# AVR.net
KiCad netlist of a schematic drawn in EAGLE
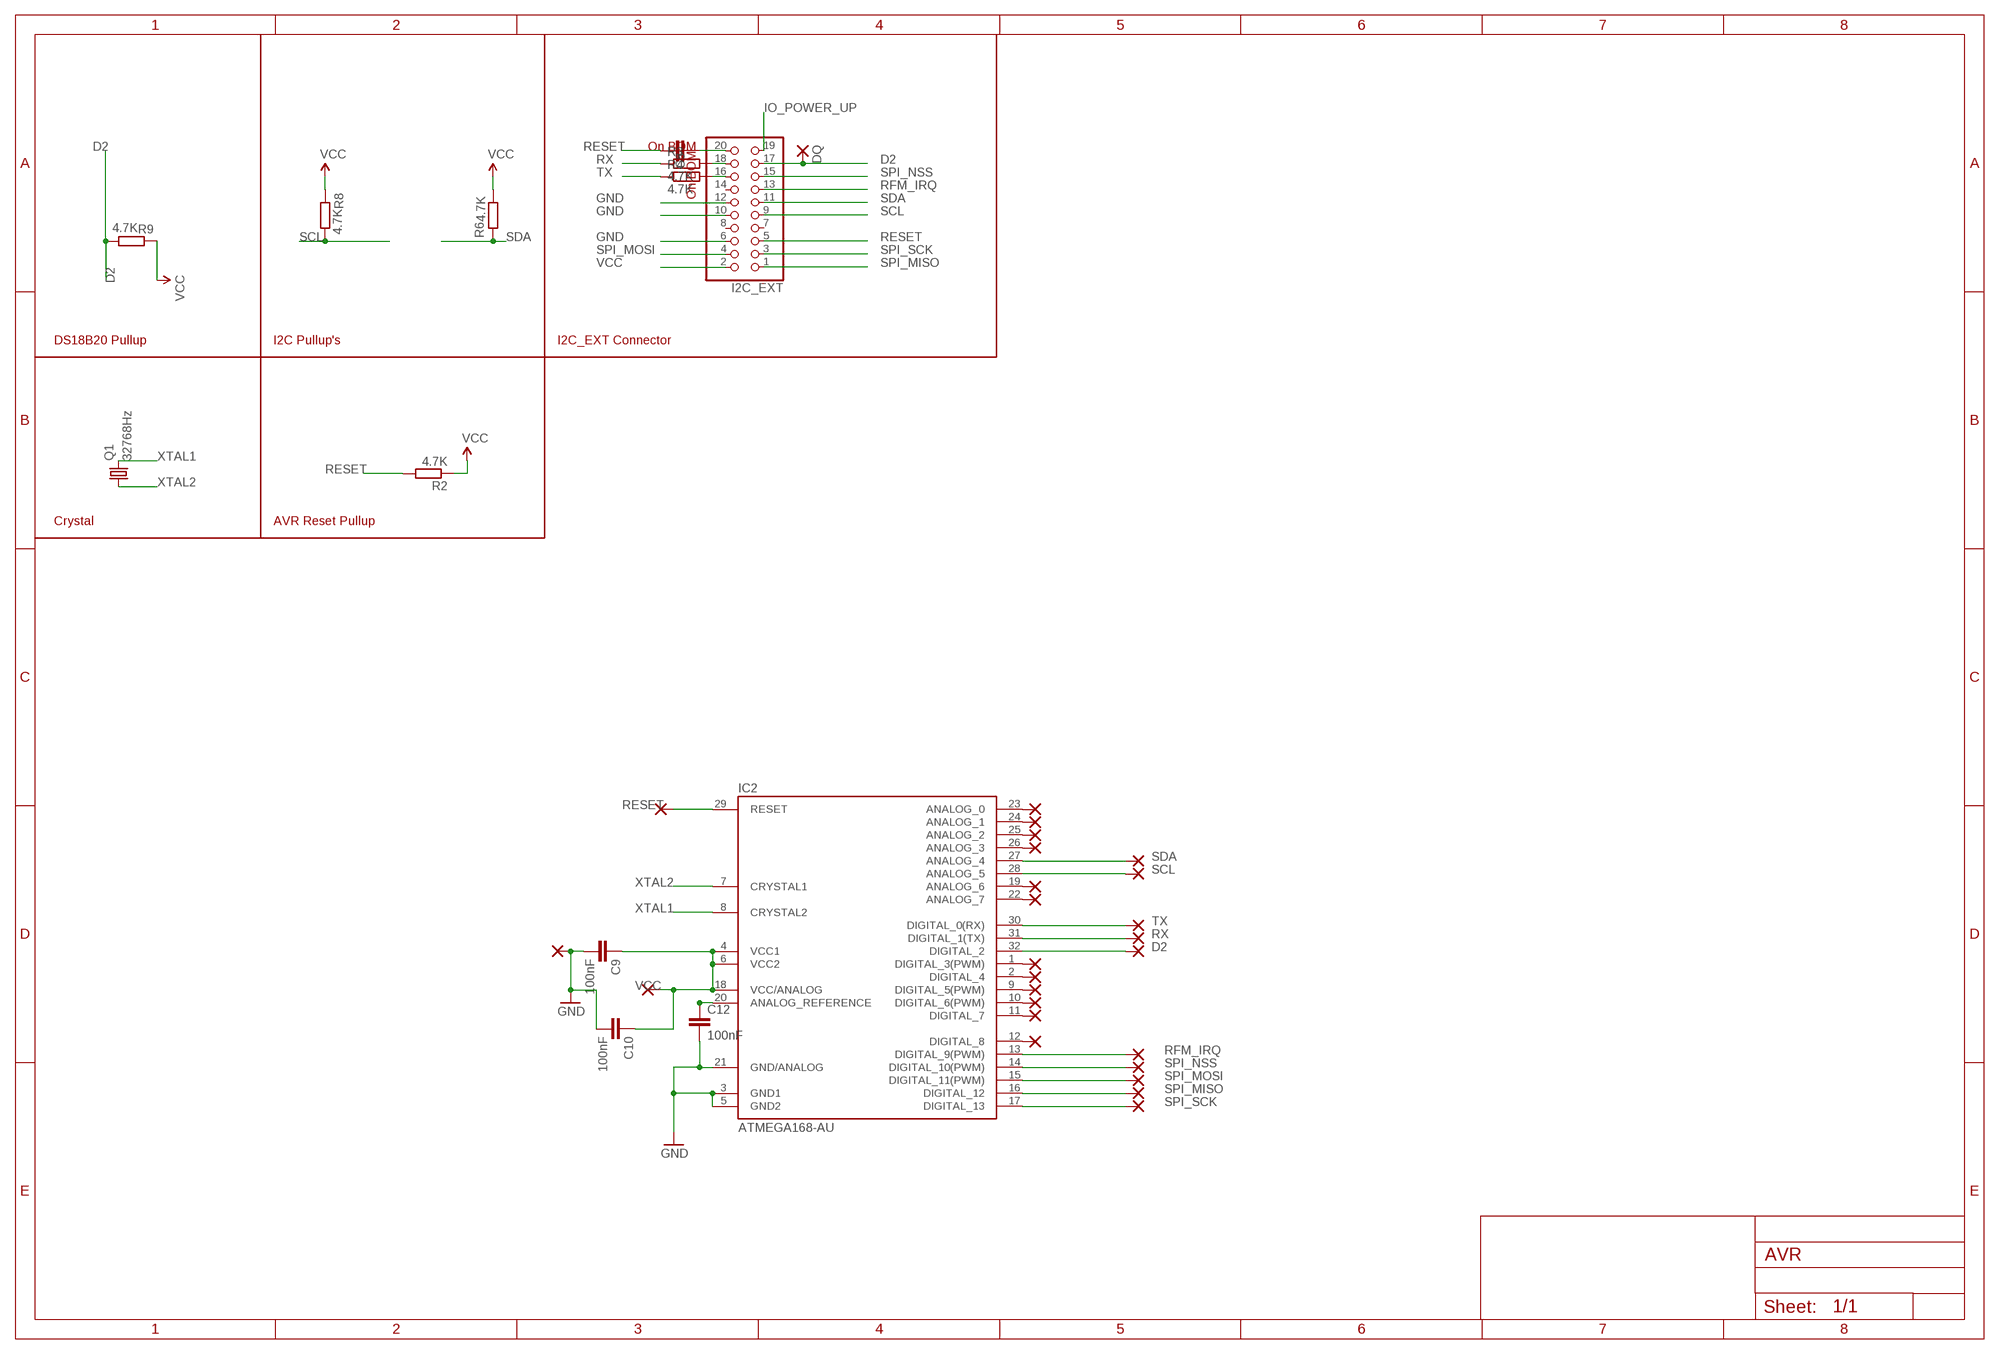
[diagram p0: schematic, sheet 1]

(export (version "E")
  (design (tool "Eeschema 10.0.6"))
  (components
    (comp (ref "C5")
      (value "100nF")
      (footprint "eagle-import:C0603")
      (libsource (lib "eagle-import") (part "C-EUC0603"))
    )
    (comp (ref "C9")
      (value "100nF")
      (footprint "eagle-import:C0603")
      (libsource (lib "eagle-import") (part "C-EUC0603"))
    )
    (comp (ref "C10")
      (value "100nF")
      (footprint "eagle-import:C0603")
      (libsource (lib "eagle-import") (part "C-EUC0603"))
    )
    (comp (ref "C12")
      (value "100nF")
      (footprint "eagle-import:C0603")
      (libsource (lib "eagle-import") (part "C-EUC0603"))
    )
    (comp (ref "DQ")
      (value "2,15/1,0")
      (footprint "eagle-import:2,15_1,0")
      (libsource (lib "eagle-import") (part "2,15/1,0"))
    )
    (comp (ref "I2C_EXT")
      (value "PINHD-2X10")
      (footprint "eagle-import:2X10")
      (libsource (lib "eagle-import") (part "PINHD-2X10"))
    )
    (comp (ref "IC2")
      (value "ATMEGA168-AU")
      (footprint "eagle-import:TQFP32-08")
      (libsource (lib "eagle-import") (part "ATMEGA168-AU"))
    )
    (comp (ref "PAD1")
      (value "1,6/0,8")
      (footprint "eagle-import:1,6_0,8")
      (libsource (lib "eagle-import") (part "1,6/0,8"))
    )
    (comp (ref "PAD2")
      (value "1,6/0,8")
      (footprint "eagle-import:1,6_0,8")
      (libsource (lib "eagle-import") (part "1,6/0,8"))
    )
    (comp (ref "PAD3")
      (value "1,6/0,8")
      (footprint "eagle-import:1,6_0,8")
      (libsource (lib "eagle-import") (part "1,6/0,8"))
    )
    (comp (ref "PAD4")
      (value "1,6/0,8")
      (footprint "eagle-import:1,6_0,8")
      (libsource (lib "eagle-import") (part "1,6/0,8"))
    )
    (comp (ref "PAD5")
      (value "1,6/0,8")
      (footprint "eagle-import:1,6_0,8")
      (libsource (lib "eagle-import") (part "1,6/0,8"))
    )
    (comp (ref "PAD6")
      (value "1,6/0,8")
      (footprint "eagle-import:1,6_0,8")
      (libsource (lib "eagle-import") (part "1,6/0,8"))
    )
    (comp (ref "PAD7")
      (value "1,6/0,8")
      (footprint "eagle-import:1,6_0,8")
      (libsource (lib "eagle-import") (part "1,6/0,8"))
    )
    (comp (ref "PAD8")
      (value "1,6/0,8")
      (footprint "eagle-import:1,6_0,8")
      (libsource (lib "eagle-import") (part "1,6/0,8"))
    )
    (comp (ref "PAD9")
      (value "1,6/0,8")
      (footprint "eagle-import:1,6_0,8")
      (libsource (lib "eagle-import") (part "1,6/0,8"))
    )
    (comp (ref "PAD10")
      (value "1,6/0,8")
      (footprint "eagle-import:1,6_0,8")
      (libsource (lib "eagle-import") (part "1,6/0,8"))
    )
    (comp (ref "PAD11")
      (value "1,6/0,8")
      (footprint "eagle-import:1,6_0,8")
      (libsource (lib "eagle-import") (part "1,6/0,8"))
    )
    (comp (ref "PAD12")
      (value "1,6/0,8")
      (footprint "eagle-import:1,6_0,8")
      (libsource (lib "eagle-import") (part "1,6/0,8"))
    )
    (comp (ref "PAD13")
      (value "1,6/0,8")
      (footprint "eagle-import:1,6_0,8")
      (libsource (lib "eagle-import") (part "1,6/0,8"))
    )
    (comp (ref "PAD14")
      (value "1,6/0,8")
      (footprint "eagle-import:1,6_0,8")
      (libsource (lib "eagle-import") (part "1,6/0,8"))
    )
    (comp (ref "PAD15")
      (value "1,6/0,8")
      (footprint "eagle-import:1,6_0,8")
      (libsource (lib "eagle-import") (part "1,6/0,8"))
    )
    (comp (ref "PAD16")
      (value "1,6/0,8")
      (footprint "eagle-import:1,6_0,8")
      (libsource (lib "eagle-import") (part "1,6/0,8"))
    )
    (comp (ref "PAD17")
      (value "1,6/0,8")
      (footprint "eagle-import:1,6_0,8")
      (libsource (lib "eagle-import") (part "1,6/0,8"))
    )
    (comp (ref "PAD18")
      (value "1,6/0,8")
      (footprint "eagle-import:1,6_0,8")
      (libsource (lib "eagle-import") (part "1,6/0,8"))
    )
    (comp (ref "PAD19")
      (value "1,6/0,8")
      (footprint "eagle-import:1,6_0,8")
      (libsource (lib "eagle-import") (part "1,6/0,8"))
    )
    (comp (ref "PAD20")
      (value "1,6/0,8")
      (footprint "eagle-import:1,6_0,8")
      (libsource (lib "eagle-import") (part "1,6/0,8"))
    )
    (comp (ref "PAD21")
      (value "1,6/0,8")
      (footprint "eagle-import:1,6_0,8")
      (libsource (lib "eagle-import") (part "1,6/0,8"))
    )
    (comp (ref "PAD22")
      (value "1,6/0,8")
      (footprint "eagle-import:1,6_0,8")
      (libsource (lib "eagle-import") (part "1,6/0,8"))
    )
    (comp (ref "PAD23")
      (value "1,6/0,8")
      (footprint "eagle-import:1,6_0,8")
      (libsource (lib "eagle-import") (part "1,6/0,8"))
    )
    (comp (ref "PAD24")
      (value "1,6/0,8")
      (footprint "eagle-import:1,6_0,8")
      (libsource (lib "eagle-import") (part "1,6/0,8"))
    )
    (comp (ref "PAD25")
      (value "1,6/0,8")
      (footprint "eagle-import:1,6_0,8")
      (libsource (lib "eagle-import") (part "1,6/0,8"))
    )
    (comp (ref "Q1")
      (value "32768Hz")
      (footprint "eagle-import:MC-306")
      (fields (field (name "MPN") "MC-306 60.0KHZ  100PPM ,12.5PF"))
      (libsource (lib "eagle-import") (part "MC-306"))
    )
    (comp (ref "R2")
      (value "4.7K")
      (footprint "eagle-import:R0603")
      (libsource (lib "eagle-import") (part "R-EU_R0603"))
    )
    (comp (ref "R3")
      (value "4.7K")
      (footprint "eagle-import:R0603")
      (libsource (lib "eagle-import") (part "R-EU_R0603"))
    )
    (comp (ref "R4")
      (value "4.7K")
      (footprint "eagle-import:R0603")
      (libsource (lib "eagle-import") (part "R-EU_R0603"))
    )
    (comp (ref "R6")
      (value "4.7K")
      (footprint "eagle-import:R0603")
      (libsource (lib "eagle-import") (part "R-EU_R0603"))
    )
    (comp (ref "R8")
      (value "4.7K")
      (footprint "eagle-import:R0603")
      (libsource (lib "eagle-import") (part "R-EU_R0603"))
    )
    (comp (ref "R9")
      (value "4.7K")
      (footprint "eagle-import:R0603")
      (libsource (lib "eagle-import") (part "R-EU_R0603"))
    )
  )
  (nets
    (net (code "1") (name "/D2") (class "Default")
      (node (ref "DQ") (pin "1") (pinfunction "P_1") (pintype "passive"))
      (node (ref "I2C_EXT") (pin "17") (pinfunction "17_17") (pintype "passive"))
      (node (ref "IC2") (pin "32") (pinfunction "DIGITAL_2_32") (pintype "bidirectional"))
      (node (ref "PAD14") (pin "1") (pinfunction "P_1") (pintype "passive"))
      (node (ref "R9") (pin "1") (pinfunction "1_1") (pintype "passive"))
    )
    (net (code "2") (name "/IO_POWER_UP") (class "Default")
      (node (ref "I2C_EXT") (pin "19") (pinfunction "19_19") (pintype "passive"))
    )
    (net (code "3") (name "/RESET") (class "Default")
      (node (ref "C5") (pin "1") (pinfunction "1_1") (pintype "passive"))
      (node (ref "I2C_EXT") (pin "5") (pinfunction "5_5") (pintype "passive"))
      (node (ref "IC2") (pin "29") (pinfunction "RESET_29") (pintype "bidirectional"))
      (node (ref "PAD1") (pin "1") (pinfunction "P_1") (pintype "passive"))
      (node (ref "R2") (pin "2") (pinfunction "2_2") (pintype "passive"))
    )
    (net (code "4") (name "/RFM_IRQ") (class "Default")
      (node (ref "I2C_EXT") (pin "13") (pinfunction "13_13") (pintype "passive"))
      (node (ref "IC2") (pin "13") (pinfunction "DIGITAL_9(PWM)_13") (pintype "bidirectional"))
      (node (ref "PAD21") (pin "1") (pinfunction "P_1") (pintype "passive"))
    )
    (net (code "5") (name "/RX") (class "Default")
      (node (ref "IC2") (pin "31") (pinfunction "DIGITAL_1(TX)_31") (pintype "bidirectional"))
      (node (ref "PAD13") (pin "1") (pinfunction "P_1") (pintype "passive"))
      (node (ref "R3") (pin "1") (pinfunction "1_1") (pintype "passive"))
    )
    (net (code "6") (name "/SCL") (class "Default")
      (node (ref "I2C_EXT") (pin "9") (pinfunction "9_9") (pintype "passive"))
      (node (ref "IC2") (pin "28") (pinfunction "ANALOG_5_28") (pintype "bidirectional"))
      (node (ref "PAD9") (pin "1") (pinfunction "P_1") (pintype "passive"))
      (node (ref "R8") (pin "1") (pinfunction "1_1") (pintype "passive"))
    )
    (net (code "7") (name "/SDA") (class "Default")
      (node (ref "I2C_EXT") (pin "11") (pinfunction "11_11") (pintype "passive"))
      (node (ref "IC2") (pin "27") (pinfunction "ANALOG_4_27") (pintype "bidirectional"))
      (node (ref "PAD8") (pin "1") (pinfunction "P_1") (pintype "passive"))
      (node (ref "R6") (pin "2") (pinfunction "2_2") (pintype "passive"))
    )
    (net (code "8") (name "/SPI_MISO") (class "Default")
      (node (ref "I2C_EXT") (pin "1") (pinfunction "1_1") (pintype "passive"))
      (node (ref "IC2") (pin "16") (pinfunction "DIGITAL_12_16") (pintype "bidirectional"))
      (node (ref "PAD24") (pin "1") (pinfunction "P_1") (pintype "passive"))
    )
    (net (code "9") (name "/SPI_MOSI") (class "Default")
      (node (ref "I2C_EXT") (pin "4") (pinfunction "4_4") (pintype "passive"))
      (node (ref "IC2") (pin "15") (pinfunction "DIGITAL_11(PWM)_15") (pintype "bidirectional"))
      (node (ref "PAD23") (pin "1") (pinfunction "P_1") (pintype "passive"))
    )
    (net (code "10") (name "/SPI_NSS") (class "Default")
      (node (ref "I2C_EXT") (pin "15") (pinfunction "15_15") (pintype "passive"))
      (node (ref "IC2") (pin "14") (pinfunction "DIGITAL_10(PWM)_14") (pintype "bidirectional"))
      (node (ref "PAD22") (pin "1") (pinfunction "P_1") (pintype "passive"))
    )
    (net (code "11") (name "/SPI_SCK") (class "Default")
      (node (ref "I2C_EXT") (pin "3") (pinfunction "3_3") (pintype "passive"))
      (node (ref "IC2") (pin "17") (pinfunction "DIGITAL_13_17") (pintype "bidirectional"))
      (node (ref "PAD25") (pin "1") (pinfunction "P_1") (pintype "passive"))
    )
    (net (code "12") (name "/TX") (class "Default")
      (node (ref "IC2") (pin "30") (pinfunction "DIGITAL_0(RX)_30") (pintype "bidirectional"))
      (node (ref "PAD12") (pin "1") (pinfunction "P_1") (pintype "passive"))
      (node (ref "R4") (pin "1") (pinfunction "1_1") (pintype "passive"))
    )
    (net (code "13") (name "/XTAL1") (class "Default")
      (node (ref "IC2") (pin "8") (pinfunction "CRYSTAL2_8") (pintype "bidirectional"))
      (node (ref "Q1") (pin "4") (pinfunction "2_4") (pintype "passive"))
    )
    (net (code "14") (name "/XTAL2") (class "Default")
      (node (ref "IC2") (pin "7") (pinfunction "CRYSTAL1_7") (pintype "bidirectional"))
      (node (ref "Q1") (pin "1") (pinfunction "1_1") (pintype "passive"))
    )
    (net (code "15") (name "GND") (class "Default")
      (node (ref "C10") (pin "2") (pinfunction "2_2") (pintype "passive"))
      (node (ref "C12") (pin "2") (pinfunction "2_2") (pintype "passive"))
      (node (ref "C9") (pin "2") (pinfunction "2_2") (pintype "passive"))
      (node (ref "I2C_EXT") (pin "10") (pinfunction "10_10") (pintype "passive"))
      (node (ref "I2C_EXT") (pin "12") (pinfunction "12_12") (pintype "passive"))
      (node (ref "I2C_EXT") (pin "6") (pinfunction "6_6") (pintype "passive"))
      (node (ref "IC2") (pin "21") (pinfunction "GND/ANALOG_21") (pintype "power_in"))
      (node (ref "IC2") (pin "3") (pinfunction "GND1_3") (pintype "power_in"))
      (node (ref "IC2") (pin "5") (pinfunction "GND2_5") (pintype "power_in"))
      (node (ref "PAD2") (pin "1") (pinfunction "P_1") (pintype "passive"))
    )
    (net (code "16") (name "Net-(C5-Pad2)") (class "Default")
      (node (ref "C5") (pin "2") (pinfunction "2_2") (pintype "passive"))
      (node (ref "I2C_EXT") (pin "20") (pinfunction "20_20") (pintype "passive"))
    )
    (net (code "17") (name "Net-(I2C_EXT-Pad16)") (class "Default")
      (node (ref "I2C_EXT") (pin "16") (pinfunction "16_16") (pintype "passive"))
      (node (ref "R4") (pin "2") (pinfunction "2_2") (pintype "passive"))
    )
    (net (code "18") (name "Net-(I2C_EXT-Pad18)") (class "Default")
      (node (ref "I2C_EXT") (pin "18") (pinfunction "18_18") (pintype "passive"))
      (node (ref "R3") (pin "2") (pinfunction "2_2") (pintype "passive"))
    )
    (net (code "19") (name "Net-(IC2-ANALOG_0)") (class "Default")
      (node (ref "IC2") (pin "23") (pinfunction "ANALOG_0_23") (pintype "bidirectional"))
      (node (ref "PAD4") (pin "1") (pinfunction "P_1") (pintype "passive"))
    )
    (net (code "20") (name "Net-(IC2-ANALOG_1)") (class "Default")
      (node (ref "IC2") (pin "24") (pinfunction "ANALOG_1_24") (pintype "bidirectional"))
      (node (ref "PAD5") (pin "1") (pinfunction "P_1") (pintype "passive"))
    )
    (net (code "21") (name "Net-(IC2-ANALOG_2)") (class "Default")
      (node (ref "IC2") (pin "25") (pinfunction "ANALOG_2_25") (pintype "bidirectional"))
      (node (ref "PAD6") (pin "1") (pinfunction "P_1") (pintype "passive"))
    )
    (net (code "22") (name "Net-(IC2-ANALOG_3)") (class "Default")
      (node (ref "IC2") (pin "26") (pinfunction "ANALOG_3_26") (pintype "bidirectional"))
      (node (ref "PAD7") (pin "1") (pinfunction "P_1") (pintype "passive"))
    )
    (net (code "23") (name "Net-(IC2-ANALOG_6)") (class "Default")
      (node (ref "IC2") (pin "19") (pinfunction "ANALOG_6_19") (pintype "passive"))
      (node (ref "PAD10") (pin "1") (pinfunction "P_1") (pintype "passive"))
    )
    (net (code "24") (name "Net-(IC2-ANALOG_7)") (class "Default")
      (node (ref "IC2") (pin "22") (pinfunction "ANALOG_7_22") (pintype "passive"))
      (node (ref "PAD11") (pin "1") (pinfunction "P_1") (pintype "passive"))
    )
    (net (code "25") (name "Net-(IC2-ANALOG_REFERENCE)") (class "Default")
      (node (ref "C12") (pin "1") (pinfunction "1_1") (pintype "passive"))
      (node (ref "IC2") (pin "20") (pinfunction "ANALOG_REFERENCE_20") (pintype "passive"))
    )
    (net (code "26") (name "Net-(IC2-DIGITAL_3(PWM))") (class "Default")
      (node (ref "IC2") (pin "1") (pinfunction "DIGITAL_3(PWM)_1") (pintype "bidirectional"))
      (node (ref "PAD15") (pin "1") (pinfunction "P_1") (pintype "passive"))
    )
    (net (code "27") (name "Net-(IC2-DIGITAL_4)") (class "Default")
      (node (ref "IC2") (pin "2") (pinfunction "DIGITAL_4_2") (pintype "bidirectional"))
      (node (ref "PAD16") (pin "1") (pinfunction "P_1") (pintype "passive"))
    )
    (net (code "28") (name "Net-(IC2-DIGITAL_5(PWM))") (class "Default")
      (node (ref "IC2") (pin "9") (pinfunction "DIGITAL_5(PWM)_9") (pintype "bidirectional"))
      (node (ref "PAD17") (pin "1") (pinfunction "P_1") (pintype "passive"))
    )
    (net (code "29") (name "Net-(IC2-DIGITAL_6(PWM))") (class "Default")
      (node (ref "IC2") (pin "10") (pinfunction "DIGITAL_6(PWM)_10") (pintype "bidirectional"))
      (node (ref "PAD18") (pin "1") (pinfunction "P_1") (pintype "passive"))
    )
    (net (code "30") (name "Net-(IC2-DIGITAL_7)") (class "Default")
      (node (ref "IC2") (pin "11") (pinfunction "DIGITAL_7_11") (pintype "bidirectional"))
      (node (ref "PAD19") (pin "1") (pinfunction "P_1") (pintype "passive"))
    )
    (net (code "31") (name "Net-(IC2-DIGITAL_8)") (class "Default")
      (node (ref "IC2") (pin "12") (pinfunction "DIGITAL_8_12") (pintype "bidirectional"))
      (node (ref "PAD20") (pin "1") (pinfunction "P_1") (pintype "passive"))
    )
    (net (code "32") (name "VCC") (class "Default")
      (node (ref "C10") (pin "1") (pinfunction "1_1") (pintype "passive"))
      (node (ref "C9") (pin "1") (pinfunction "1_1") (pintype "passive"))
      (node (ref "I2C_EXT") (pin "2") (pinfunction "2_2") (pintype "passive"))
      (node (ref "IC2") (pin "18") (pinfunction "VCC/ANALOG_18") (pintype "passive"))
      (node (ref "IC2") (pin "4") (pinfunction "VCC1_4") (pintype "power_in"))
      (node (ref "IC2") (pin "6") (pinfunction "VCC2_6") (pintype "power_in"))
      (node (ref "PAD3") (pin "1") (pinfunction "P_1") (pintype "passive"))
      (node (ref "R2") (pin "1") (pinfunction "1_1") (pintype "passive"))
      (node (ref "R6") (pin "1") (pinfunction "1_1") (pintype "passive"))
      (node (ref "R8") (pin "2") (pinfunction "2_2") (pintype "passive"))
      (node (ref "R9") (pin "2") (pinfunction "2_2") (pintype "passive"))
    )
    (net (code "33") (name "unconnected-(I2C_EXT-Pad7)") (class "Default")
      (node (ref "I2C_EXT") (pin "7") (pinfunction "7_7") (pintype "passive"))
    )
    (net (code "34") (name "unconnected-(I2C_EXT-Pad8)") (class "Default")
      (node (ref "I2C_EXT") (pin "8") (pinfunction "8_8") (pintype "passive"))
    )
    (net (code "35") (name "unconnected-(I2C_EXT-Pad14)") (class "Default")
      (node (ref "I2C_EXT") (pin "14") (pinfunction "14_14") (pintype "passive"))
    )
  )
)
